# W603A.net
KiCad netlist of a schematic drawn in EAGLE
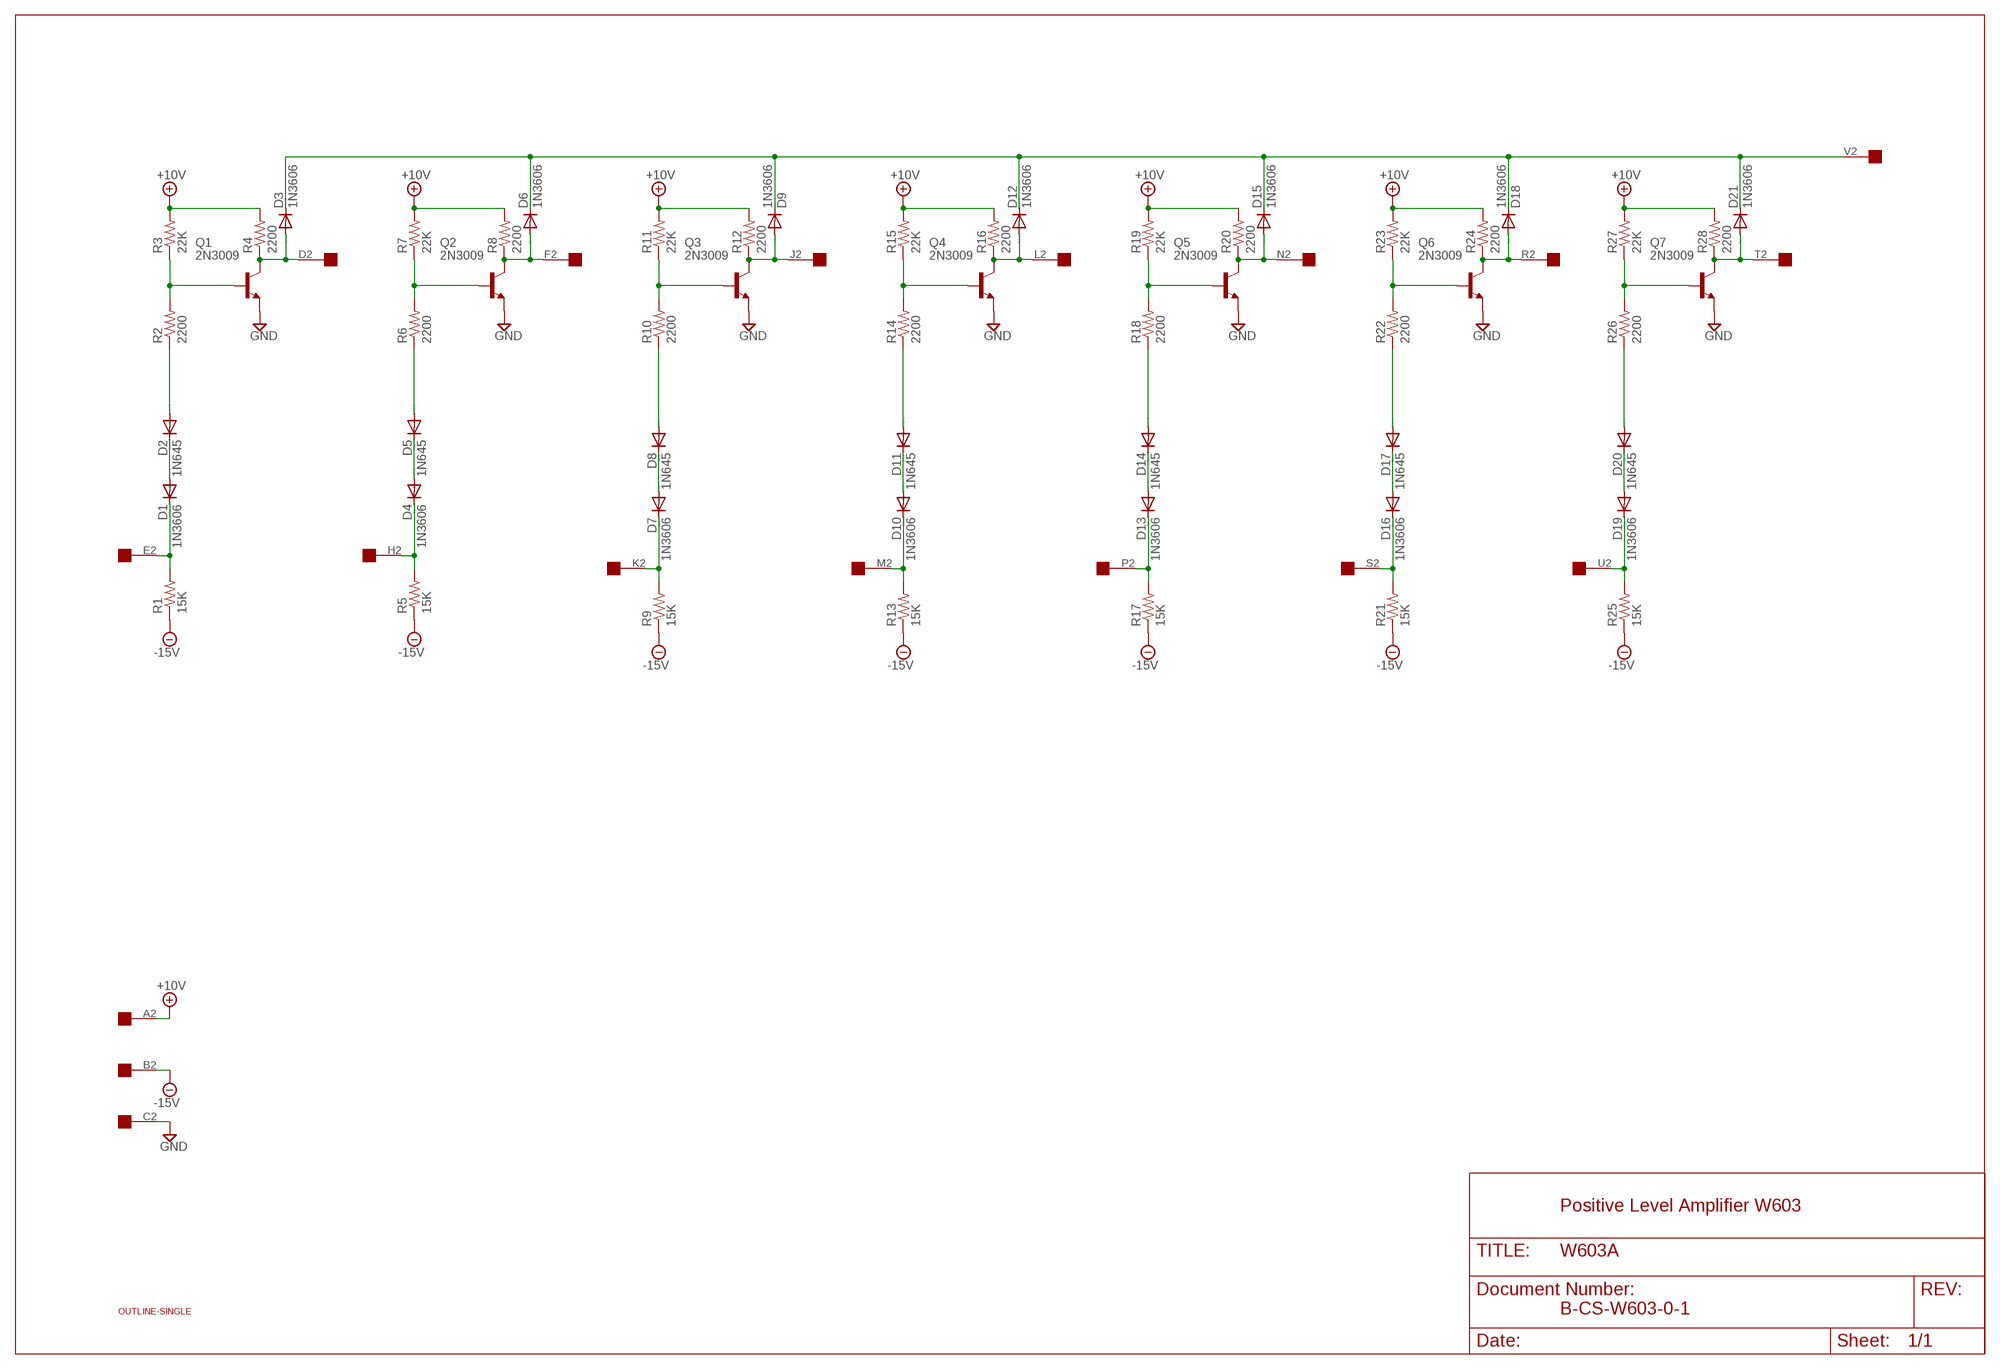
[diagram p0: schematic, sheet 1]

(export (version "E")
  (design (tool "Eeschema 10.0.6"))
  (components
    (comp (ref "D1")
      (value "1N3606")
      (footprint "eagle-import:DO35-10")
      (libsource (lib "eagle-import") (part "1N4148DO35-10"))
    )
    (comp (ref "D2")
      (value "1N645")
      (footprint "eagle-import:DO35-10")
      (libsource (lib "eagle-import") (part "1N4148DO35-10"))
    )
    (comp (ref "D3")
      (value "1N3606")
      (footprint "eagle-import:DO35-10")
      (libsource (lib "eagle-import") (part "1N4148DO35-10"))
    )
    (comp (ref "D4")
      (value "1N3606")
      (footprint "eagle-import:DO35-10")
      (libsource (lib "eagle-import") (part "1N4148DO35-10"))
    )
    (comp (ref "D5")
      (value "1N645")
      (footprint "eagle-import:DO35-10")
      (libsource (lib "eagle-import") (part "1N4148DO35-10"))
    )
    (comp (ref "D6")
      (value "1N3606")
      (footprint "eagle-import:DO35-10")
      (libsource (lib "eagle-import") (part "1N4148DO35-10"))
    )
    (comp (ref "D7")
      (value "1N3606")
      (footprint "eagle-import:DO35-10")
      (libsource (lib "eagle-import") (part "1N4148DO35-10"))
    )
    (comp (ref "D8")
      (value "1N645")
      (footprint "eagle-import:DO35-10")
      (libsource (lib "eagle-import") (part "1N4148DO35-10"))
    )
    (comp (ref "D9")
      (value "1N3606")
      (footprint "eagle-import:DO35-10")
      (libsource (lib "eagle-import") (part "1N4148DO35-10"))
    )
    (comp (ref "D10")
      (value "1N3606")
      (footprint "eagle-import:DO35-10")
      (libsource (lib "eagle-import") (part "1N4148DO35-10"))
    )
    (comp (ref "D11")
      (value "1N645")
      (footprint "eagle-import:DO35-10")
      (libsource (lib "eagle-import") (part "1N4148DO35-10"))
    )
    (comp (ref "D12")
      (value "1N3606")
      (footprint "eagle-import:DO35-10")
      (libsource (lib "eagle-import") (part "1N4148DO35-10"))
    )
    (comp (ref "D13")
      (value "1N3606")
      (footprint "eagle-import:DO35-10")
      (libsource (lib "eagle-import") (part "1N4148DO35-10"))
    )
    (comp (ref "D14")
      (value "1N645")
      (footprint "eagle-import:DO35-10")
      (libsource (lib "eagle-import") (part "1N4148DO35-10"))
    )
    (comp (ref "D15")
      (value "1N3606")
      (footprint "eagle-import:DO35-10")
      (libsource (lib "eagle-import") (part "1N4148DO35-10"))
    )
    (comp (ref "D16")
      (value "1N3606")
      (footprint "eagle-import:DO35-10")
      (libsource (lib "eagle-import") (part "1N4148DO35-10"))
    )
    (comp (ref "D17")
      (value "1N645")
      (footprint "eagle-import:DO35-10")
      (libsource (lib "eagle-import") (part "1N4148DO35-10"))
    )
    (comp (ref "D18")
      (value "1N3606")
      (footprint "eagle-import:DO35-10")
      (libsource (lib "eagle-import") (part "1N4148DO35-10"))
    )
    (comp (ref "D19")
      (value "1N3606")
      (footprint "eagle-import:DO35-10")
      (libsource (lib "eagle-import") (part "1N4148DO35-10"))
    )
    (comp (ref "D20")
      (value "1N645")
      (footprint "eagle-import:DO35-10")
      (libsource (lib "eagle-import") (part "1N4148DO35-10"))
    )
    (comp (ref "D21")
      (value "1N3606")
      (footprint "eagle-import:DO35-10")
      (libsource (lib "eagle-import") (part "1N4148DO35-10"))
    )
    (comp (ref "Q1")
      (value "2N3009")
      (footprint "eagle-import:TO5")
      (libsource (lib "eagle-import") (part "2N2102"))
    )
    (comp (ref "Q2")
      (value "2N3009")
      (footprint "eagle-import:TO5")
      (libsource (lib "eagle-import") (part "2N2102"))
    )
    (comp (ref "Q3")
      (value "2N3009")
      (footprint "eagle-import:TO5")
      (libsource (lib "eagle-import") (part "2N2102"))
    )
    (comp (ref "Q4")
      (value "2N3009")
      (footprint "eagle-import:TO5")
      (libsource (lib "eagle-import") (part "2N2102"))
    )
    (comp (ref "Q5")
      (value "2N3009")
      (footprint "eagle-import:TO5")
      (libsource (lib "eagle-import") (part "2N2102"))
    )
    (comp (ref "Q6")
      (value "2N3009")
      (footprint "eagle-import:TO5")
      (libsource (lib "eagle-import") (part "2N2102"))
    )
    (comp (ref "Q7")
      (value "2N3009")
      (footprint "eagle-import:TO5")
      (libsource (lib "eagle-import") (part "2N2102"))
    )
    (comp (ref "R1")
      (value "15K")
      (footprint "eagle-import:0207_10")
      (libsource (lib "eagle-import") (part "R-US_0207/10"))
    )
    (comp (ref "R2")
      (value "2200")
      (footprint "eagle-import:0207_10")
      (libsource (lib "eagle-import") (part "R-US_0207/10"))
    )
    (comp (ref "R3")
      (value "22K")
      (footprint "eagle-import:0207_10")
      (libsource (lib "eagle-import") (part "R-US_0207/10"))
    )
    (comp (ref "R4")
      (value "2200")
      (footprint "eagle-import:0207_10")
      (libsource (lib "eagle-import") (part "R-US_0207/10"))
    )
    (comp (ref "R5")
      (value "15K")
      (footprint "eagle-import:0207_10")
      (libsource (lib "eagle-import") (part "R-US_0207/10"))
    )
    (comp (ref "R6")
      (value "2200")
      (footprint "eagle-import:0207_10")
      (libsource (lib "eagle-import") (part "R-US_0207/10"))
    )
    (comp (ref "R7")
      (value "22K")
      (footprint "eagle-import:0207_10")
      (libsource (lib "eagle-import") (part "R-US_0207/10"))
    )
    (comp (ref "R8")
      (value "2200")
      (footprint "eagle-import:0207_10")
      (libsource (lib "eagle-import") (part "R-US_0207/10"))
    )
    (comp (ref "R9")
      (value "15K")
      (footprint "eagle-import:0207_10")
      (libsource (lib "eagle-import") (part "R-US_0207/10"))
    )
    (comp (ref "R10")
      (value "2200")
      (footprint "eagle-import:0207_10")
      (libsource (lib "eagle-import") (part "R-US_0207/10"))
    )
    (comp (ref "R11")
      (value "22K")
      (footprint "eagle-import:0207_10")
      (libsource (lib "eagle-import") (part "R-US_0207/10"))
    )
    (comp (ref "R12")
      (value "2200")
      (footprint "eagle-import:0207_10")
      (libsource (lib "eagle-import") (part "R-US_0207/10"))
    )
    (comp (ref "R13")
      (value "15K")
      (footprint "eagle-import:0207_10")
      (libsource (lib "eagle-import") (part "R-US_0207/10"))
    )
    (comp (ref "R14")
      (value "2200")
      (footprint "eagle-import:0207_10")
      (libsource (lib "eagle-import") (part "R-US_0207/10"))
    )
    (comp (ref "R15")
      (value "22K")
      (footprint "eagle-import:0207_10")
      (libsource (lib "eagle-import") (part "R-US_0207/10"))
    )
    (comp (ref "R16")
      (value "2200")
      (footprint "eagle-import:0207_10")
      (libsource (lib "eagle-import") (part "R-US_0207/10"))
    )
    (comp (ref "R17")
      (value "15K")
      (footprint "eagle-import:0207_10")
      (libsource (lib "eagle-import") (part "R-US_0207/10"))
    )
    (comp (ref "R18")
      (value "2200")
      (footprint "eagle-import:0207_10")
      (libsource (lib "eagle-import") (part "R-US_0207/10"))
    )
    (comp (ref "R19")
      (value "22K")
      (footprint "eagle-import:0207_10")
      (libsource (lib "eagle-import") (part "R-US_0207/10"))
    )
    (comp (ref "R20")
      (value "2200")
      (footprint "eagle-import:0207_10")
      (libsource (lib "eagle-import") (part "R-US_0207/10"))
    )
    (comp (ref "R21")
      (value "15K")
      (footprint "eagle-import:0207_10")
      (libsource (lib "eagle-import") (part "R-US_0207/10"))
    )
    (comp (ref "R22")
      (value "2200")
      (footprint "eagle-import:0207_10")
      (libsource (lib "eagle-import") (part "R-US_0207/10"))
    )
    (comp (ref "R23")
      (value "22K")
      (footprint "eagle-import:0207_10")
      (libsource (lib "eagle-import") (part "R-US_0207/10"))
    )
    (comp (ref "R24")
      (value "2200")
      (footprint "eagle-import:0207_10")
      (libsource (lib "eagle-import") (part "R-US_0207/10"))
    )
    (comp (ref "R25")
      (value "15K")
      (footprint "eagle-import:0207_10")
      (libsource (lib "eagle-import") (part "R-US_0207/10"))
    )
    (comp (ref "R26")
      (value "2200")
      (footprint "eagle-import:0207_10")
      (libsource (lib "eagle-import") (part "R-US_0207/10"))
    )
    (comp (ref "R27")
      (value "22K")
      (footprint "eagle-import:0207_10")
      (libsource (lib "eagle-import") (part "R-US_0207/10"))
    )
    (comp (ref "R28")
      (value "2200")
      (footprint "eagle-import:0207_10")
      (libsource (lib "eagle-import") (part "R-US_0207/10"))
    )
    (comp (ref "U$1")
      (value "OUTLINE-SINGLE")
      (footprint "eagle-import:SINGLE")
      (libsource (lib "eagle-import") (part "OUTLINE-SINGLE"))
    )
    (comp (ref "U$2")
      (value "EDGE-1")
      (footprint "eagle-import:EDGE-CON1")
      (libsource (lib "eagle-import") (part "EDGE-1"))
    )
  )
  (nets
    (net (code "1") (name "+10V") (class "Default")
      (node (ref "R11") (pin "2") (pinfunction "2_2") (pintype "passive"))
      (node (ref "R12") (pin "2") (pinfunction "2_2") (pintype "passive"))
      (node (ref "R15") (pin "2") (pinfunction "2_2") (pintype "passive"))
      (node (ref "R16") (pin "2") (pinfunction "2_2") (pintype "passive"))
      (node (ref "R19") (pin "2") (pinfunction "2_2") (pintype "passive"))
      (node (ref "R20") (pin "2") (pinfunction "2_2") (pintype "passive"))
      (node (ref "R23") (pin "2") (pinfunction "2_2") (pintype "passive"))
      (node (ref "R24") (pin "2") (pinfunction "2_2") (pintype "passive"))
      (node (ref "R27") (pin "2") (pinfunction "2_2") (pintype "passive"))
      (node (ref "R28") (pin "2") (pinfunction "2_2") (pintype "passive"))
      (node (ref "R3") (pin "2") (pinfunction "2_2") (pintype "passive"))
      (node (ref "R4") (pin "2") (pinfunction "2_2") (pintype "passive"))
      (node (ref "R7") (pin "2") (pinfunction "2_2") (pintype "passive"))
      (node (ref "R8") (pin "2") (pinfunction "2_2") (pintype "passive"))
      (node (ref "U$2") (pin "A2") (pinfunction "1_A2") (pintype "bidirectional"))
    )
    (net (code "2") (name "-15V") (class "Default")
      (node (ref "R1") (pin "1") (pinfunction "1_1") (pintype "passive"))
      (node (ref "R13") (pin "1") (pinfunction "1_1") (pintype "passive"))
      (node (ref "R17") (pin "1") (pinfunction "1_1") (pintype "passive"))
      (node (ref "R21") (pin "1") (pinfunction "1_1") (pintype "passive"))
      (node (ref "R25") (pin "1") (pinfunction "1_1") (pintype "passive"))
      (node (ref "R5") (pin "1") (pinfunction "1_1") (pintype "passive"))
      (node (ref "R9") (pin "1") (pinfunction "1_1") (pintype "passive"))
      (node (ref "U$2") (pin "B2") (pinfunction "1_B2") (pintype "bidirectional"))
    )
    (net (code "3") (name "GND") (class "Default")
      (node (ref "Q1") (pin "1") (pinfunction "E_1") (pintype "passive"))
      (node (ref "Q2") (pin "1") (pinfunction "E_1") (pintype "passive"))
      (node (ref "Q3") (pin "1") (pinfunction "E_1") (pintype "passive"))
      (node (ref "Q4") (pin "1") (pinfunction "E_1") (pintype "passive"))
      (node (ref "Q5") (pin "1") (pinfunction "E_1") (pintype "passive"))
      (node (ref "Q6") (pin "1") (pinfunction "E_1") (pintype "passive"))
      (node (ref "Q7") (pin "1") (pinfunction "E_1") (pintype "passive"))
      (node (ref "U$2") (pin "C2") (pinfunction "1_C2") (pintype "bidirectional"))
    )
    (net (code "4") (name "Net-(D1-PadA)") (class "Default")
      (node (ref "D1") (pin "A") (pinfunction "A_A") (pintype "passive"))
      (node (ref "D2") (pin "C") (pinfunction "C_C") (pintype "passive"))
    )
    (net (code "5") (name "Net-(D2-PadA)") (class "Default")
      (node (ref "D2") (pin "A") (pinfunction "A_A") (pintype "passive"))
      (node (ref "R2") (pin "1") (pinfunction "1_1") (pintype "passive"))
    )
    (net (code "6") (name "Net-(D4-PadA)") (class "Default")
      (node (ref "D4") (pin "A") (pinfunction "A_A") (pintype "passive"))
      (node (ref "D5") (pin "C") (pinfunction "C_C") (pintype "passive"))
    )
    (net (code "7") (name "Net-(D5-PadA)") (class "Default")
      (node (ref "D5") (pin "A") (pinfunction "A_A") (pintype "passive"))
      (node (ref "R6") (pin "1") (pinfunction "1_1") (pintype "passive"))
    )
    (net (code "8") (name "Net-(D7-PadA)") (class "Default")
      (node (ref "D7") (pin "A") (pinfunction "A_A") (pintype "passive"))
      (node (ref "D8") (pin "C") (pinfunction "C_C") (pintype "passive"))
    )
    (net (code "9") (name "Net-(D8-PadA)") (class "Default")
      (node (ref "D8") (pin "A") (pinfunction "A_A") (pintype "passive"))
      (node (ref "R10") (pin "1") (pinfunction "1_1") (pintype "passive"))
    )
    (net (code "10") (name "Net-(D10-PadA)") (class "Default")
      (node (ref "D10") (pin "A") (pinfunction "A_A") (pintype "passive"))
      (node (ref "D11") (pin "C") (pinfunction "C_C") (pintype "passive"))
    )
    (net (code "11") (name "Net-(D11-PadA)") (class "Default")
      (node (ref "D11") (pin "A") (pinfunction "A_A") (pintype "passive"))
      (node (ref "R14") (pin "1") (pinfunction "1_1") (pintype "passive"))
    )
    (net (code "12") (name "Net-(D13-PadA)") (class "Default")
      (node (ref "D13") (pin "A") (pinfunction "A_A") (pintype "passive"))
      (node (ref "D14") (pin "C") (pinfunction "C_C") (pintype "passive"))
    )
    (net (code "13") (name "Net-(D14-PadA)") (class "Default")
      (node (ref "D14") (pin "A") (pinfunction "A_A") (pintype "passive"))
      (node (ref "R18") (pin "1") (pinfunction "1_1") (pintype "passive"))
    )
    (net (code "14") (name "Net-(D16-PadA)") (class "Default")
      (node (ref "D16") (pin "A") (pinfunction "A_A") (pintype "passive"))
      (node (ref "D17") (pin "C") (pinfunction "C_C") (pintype "passive"))
    )
    (net (code "15") (name "Net-(D17-PadA)") (class "Default")
      (node (ref "D17") (pin "A") (pinfunction "A_A") (pintype "passive"))
      (node (ref "R22") (pin "1") (pinfunction "1_1") (pintype "passive"))
    )
    (net (code "16") (name "Net-(D19-PadA)") (class "Default")
      (node (ref "D19") (pin "A") (pinfunction "A_A") (pintype "passive"))
      (node (ref "D20") (pin "C") (pinfunction "C_C") (pintype "passive"))
    )
    (net (code "17") (name "Net-(D20-PadA)") (class "Default")
      (node (ref "D20") (pin "A") (pinfunction "A_A") (pintype "passive"))
      (node (ref "R26") (pin "1") (pinfunction "1_1") (pintype "passive"))
    )
    (net (code "18") (name "Net-(Q1-B)") (class "Default")
      (node (ref "Q1") (pin "2") (pinfunction "B_2") (pintype "passive"))
      (node (ref "R2") (pin "2") (pinfunction "2_2") (pintype "passive"))
      (node (ref "R3") (pin "1") (pinfunction "1_1") (pintype "passive"))
    )
    (net (code "19") (name "Net-(Q1-C)") (class "Default")
      (node (ref "D3") (pin "A") (pinfunction "A_A") (pintype "passive"))
      (node (ref "Q1") (pin "3") (pinfunction "C_3") (pintype "passive"))
      (node (ref "R4") (pin "1") (pinfunction "1_1") (pintype "passive"))
      (node (ref "U$2") (pin "D2") (pinfunction "1_D2") (pintype "bidirectional"))
    )
    (net (code "20") (name "Net-(Q2-B)") (class "Default")
      (node (ref "Q2") (pin "2") (pinfunction "B_2") (pintype "passive"))
      (node (ref "R6") (pin "2") (pinfunction "2_2") (pintype "passive"))
      (node (ref "R7") (pin "1") (pinfunction "1_1") (pintype "passive"))
    )
    (net (code "21") (name "Net-(Q2-C)") (class "Default")
      (node (ref "D6") (pin "A") (pinfunction "A_A") (pintype "passive"))
      (node (ref "Q2") (pin "3") (pinfunction "C_3") (pintype "passive"))
      (node (ref "R8") (pin "1") (pinfunction "1_1") (pintype "passive"))
      (node (ref "U$2") (pin "F2") (pinfunction "1_F2") (pintype "bidirectional"))
    )
    (net (code "22") (name "Net-(Q3-B)") (class "Default")
      (node (ref "Q3") (pin "2") (pinfunction "B_2") (pintype "passive"))
      (node (ref "R10") (pin "2") (pinfunction "2_2") (pintype "passive"))
      (node (ref "R11") (pin "1") (pinfunction "1_1") (pintype "passive"))
    )
    (net (code "23") (name "Net-(Q3-C)") (class "Default")
      (node (ref "D9") (pin "A") (pinfunction "A_A") (pintype "passive"))
      (node (ref "Q3") (pin "3") (pinfunction "C_3") (pintype "passive"))
      (node (ref "R12") (pin "1") (pinfunction "1_1") (pintype "passive"))
      (node (ref "U$2") (pin "J2") (pinfunction "1_J2") (pintype "bidirectional"))
    )
    (net (code "24") (name "Net-(Q4-B)") (class "Default")
      (node (ref "Q4") (pin "2") (pinfunction "B_2") (pintype "passive"))
      (node (ref "R14") (pin "2") (pinfunction "2_2") (pintype "passive"))
      (node (ref "R15") (pin "1") (pinfunction "1_1") (pintype "passive"))
    )
    (net (code "25") (name "Net-(Q4-C)") (class "Default")
      (node (ref "D12") (pin "A") (pinfunction "A_A") (pintype "passive"))
      (node (ref "Q4") (pin "3") (pinfunction "C_3") (pintype "passive"))
      (node (ref "R16") (pin "1") (pinfunction "1_1") (pintype "passive"))
      (node (ref "U$2") (pin "L2") (pinfunction "1_L2") (pintype "bidirectional"))
    )
    (net (code "26") (name "Net-(Q5-B)") (class "Default")
      (node (ref "Q5") (pin "2") (pinfunction "B_2") (pintype "passive"))
      (node (ref "R18") (pin "2") (pinfunction "2_2") (pintype "passive"))
      (node (ref "R19") (pin "1") (pinfunction "1_1") (pintype "passive"))
    )
    (net (code "27") (name "Net-(Q5-C)") (class "Default")
      (node (ref "D15") (pin "A") (pinfunction "A_A") (pintype "passive"))
      (node (ref "Q5") (pin "3") (pinfunction "C_3") (pintype "passive"))
      (node (ref "R20") (pin "1") (pinfunction "1_1") (pintype "passive"))
      (node (ref "U$2") (pin "N2") (pinfunction "1_N2") (pintype "bidirectional"))
    )
    (net (code "28") (name "Net-(Q6-B)") (class "Default")
      (node (ref "Q6") (pin "2") (pinfunction "B_2") (pintype "passive"))
      (node (ref "R22") (pin "2") (pinfunction "2_2") (pintype "passive"))
      (node (ref "R23") (pin "1") (pinfunction "1_1") (pintype "passive"))
    )
    (net (code "29") (name "Net-(Q6-C)") (class "Default")
      (node (ref "D18") (pin "A") (pinfunction "A_A") (pintype "passive"))
      (node (ref "Q6") (pin "3") (pinfunction "C_3") (pintype "passive"))
      (node (ref "R24") (pin "1") (pinfunction "1_1") (pintype "passive"))
      (node (ref "U$2") (pin "R2") (pinfunction "1_R2") (pintype "bidirectional"))
    )
    (net (code "30") (name "Net-(Q7-B)") (class "Default")
      (node (ref "Q7") (pin "2") (pinfunction "B_2") (pintype "passive"))
      (node (ref "R26") (pin "2") (pinfunction "2_2") (pintype "passive"))
      (node (ref "R27") (pin "1") (pinfunction "1_1") (pintype "passive"))
    )
    (net (code "31") (name "Net-(Q7-C)") (class "Default")
      (node (ref "D21") (pin "A") (pinfunction "A_A") (pintype "passive"))
      (node (ref "Q7") (pin "3") (pinfunction "C_3") (pintype "passive"))
      (node (ref "R28") (pin "1") (pinfunction "1_1") (pintype "passive"))
      (node (ref "U$2") (pin "T2") (pinfunction "1_T2") (pintype "bidirectional"))
    )
    (net (code "32") (name "Net-(U$2E-1)") (class "Default")
      (node (ref "D1") (pin "C") (pinfunction "C_C") (pintype "passive"))
      (node (ref "R1") (pin "2") (pinfunction "2_2") (pintype "passive"))
      (node (ref "U$2") (pin "E2") (pinfunction "1_E2") (pintype "bidirectional"))
    )
    (net (code "33") (name "Net-(U$2G-1)") (class "Default")
      (node (ref "D4") (pin "C") (pinfunction "C_C") (pintype "passive"))
      (node (ref "R5") (pin "2") (pinfunction "2_2") (pintype "passive"))
      (node (ref "U$2") (pin "H2") (pinfunction "1_H2") (pintype "bidirectional"))
    )
    (net (code "34") (name "Net-(U$2I-1)") (class "Default")
      (node (ref "D7") (pin "C") (pinfunction "C_C") (pintype "passive"))
      (node (ref "R9") (pin "2") (pinfunction "2_2") (pintype "passive"))
      (node (ref "U$2") (pin "K2") (pinfunction "1_K2") (pintype "bidirectional"))
    )
    (net (code "35") (name "Net-(U$2K-1)") (class "Default")
      (node (ref "D10") (pin "C") (pinfunction "C_C") (pintype "passive"))
      (node (ref "R13") (pin "2") (pinfunction "2_2") (pintype "passive"))
      (node (ref "U$2") (pin "M2") (pinfunction "1_M2") (pintype "bidirectional"))
    )
    (net (code "36") (name "Net-(U$2M-1)") (class "Default")
      (node (ref "D13") (pin "C") (pinfunction "C_C") (pintype "passive"))
      (node (ref "R17") (pin "2") (pinfunction "2_2") (pintype "passive"))
      (node (ref "U$2") (pin "P2") (pinfunction "1_P2") (pintype "bidirectional"))
    )
    (net (code "37") (name "Net-(U$2O-1)") (class "Default")
      (node (ref "D16") (pin "C") (pinfunction "C_C") (pintype "passive"))
      (node (ref "R21") (pin "2") (pinfunction "2_2") (pintype "passive"))
      (node (ref "U$2") (pin "S2") (pinfunction "1_S2") (pintype "bidirectional"))
    )
    (net (code "38") (name "Net-(U$2Q-1)") (class "Default")
      (node (ref "D19") (pin "C") (pinfunction "C_C") (pintype "passive"))
      (node (ref "R25") (pin "2") (pinfunction "2_2") (pintype "passive"))
      (node (ref "U$2") (pin "U2") (pinfunction "1_U2") (pintype "bidirectional"))
    )
    (net (code "39") (name "Net-(U$2R-1)") (class "Default")
      (node (ref "D12") (pin "C") (pinfunction "C_C") (pintype "passive"))
      (node (ref "D15") (pin "C") (pinfunction "C_C") (pintype "passive"))
      (node (ref "D18") (pin "C") (pinfunction "C_C") (pintype "passive"))
      (node (ref "D21") (pin "C") (pinfunction "C_C") (pintype "passive"))
      (node (ref "D3") (pin "C") (pinfunction "C_C") (pintype "passive"))
      (node (ref "D6") (pin "C") (pinfunction "C_C") (pintype "passive"))
      (node (ref "D9") (pin "C") (pinfunction "C_C") (pintype "passive"))
      (node (ref "U$2") (pin "V2") (pinfunction "1_V2") (pintype "bidirectional"))
    )
  )
)
